# Power.net
KiCad netlist of a schematic drawn in Altium Designer
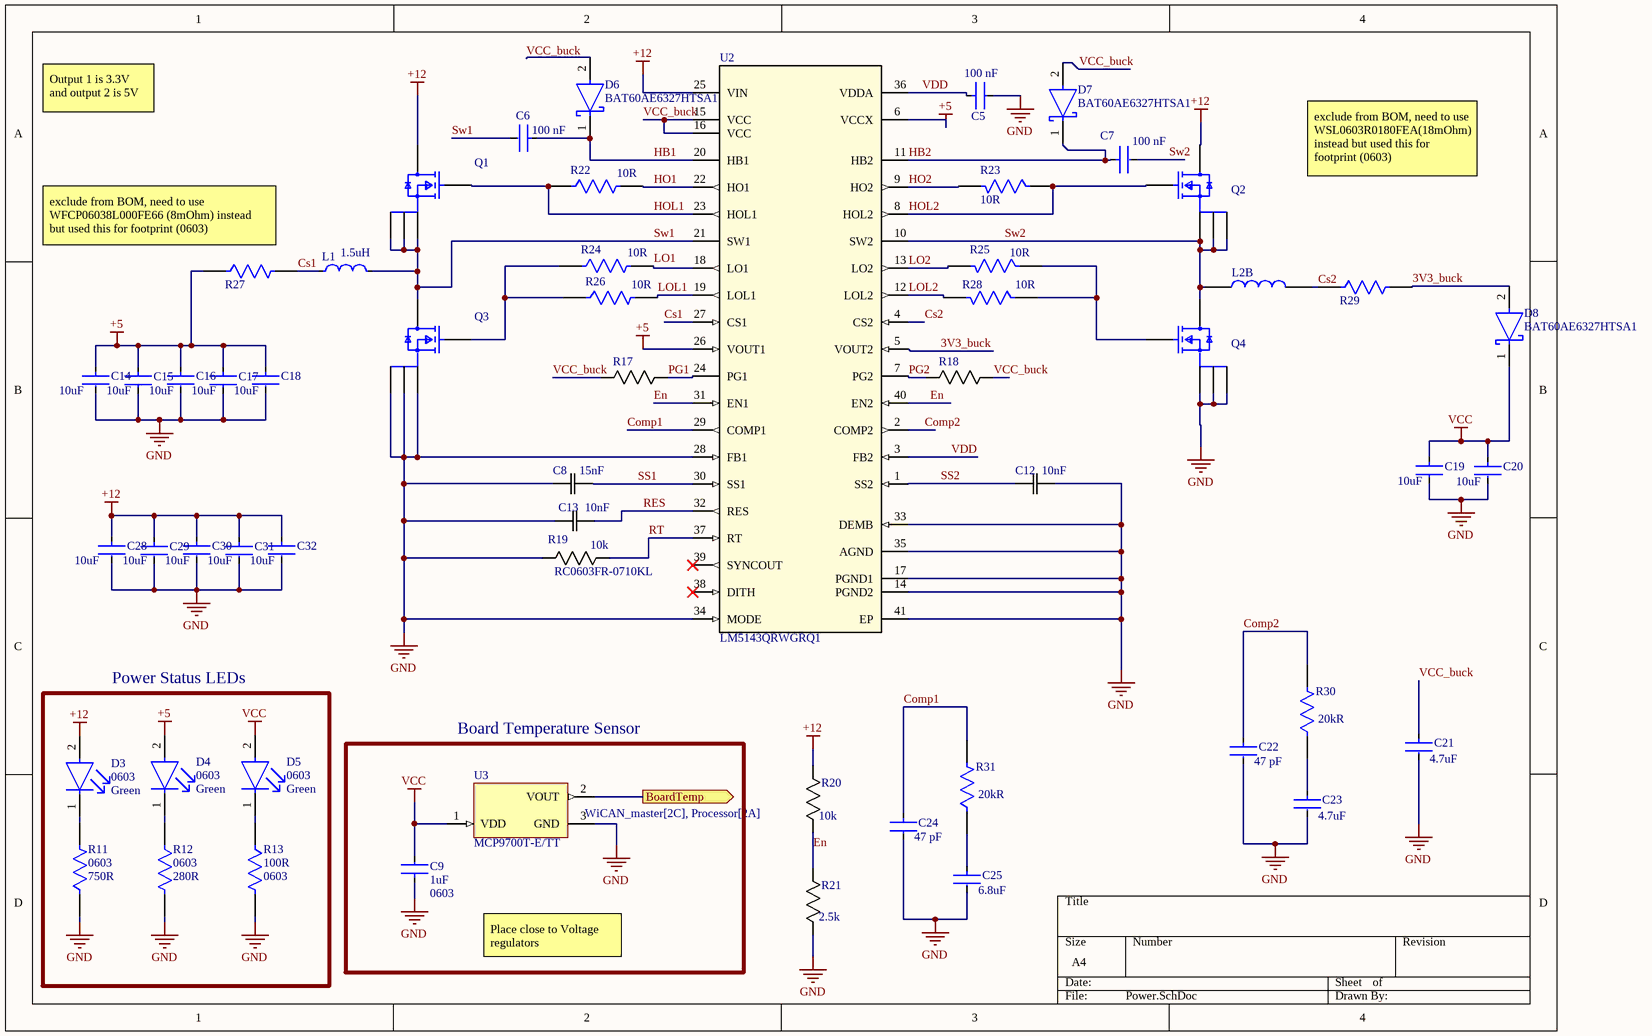
[diagram p0: Power.SchDoc]

(export (version "E")
  (design (tool "Eeschema 10.0.6"))
  (components
    (comp (ref "C5")
      (value "CC0603KRX7R8BB104")
      (footprint "FP-CC0603-DA-MFG")
      (description "CAP CER 0.1UF 25V X7R 0603")
      (fields
        (field (name "CAPACITANCE") "100 nF")
        (field (name "MANUFACTURER") "YAGEO")
        (field (name "OCTOPART") "https://octopart.com/cc0603krx7r8bb104-yageo-8376534")
      )
      (libsource (lib "Altium Content Vault") (part "11868f565c42a9108669ba33697ecf6"))
    )
    (comp (ref "C6")
      (value "CC0603KRX7R8BB104")
      (footprint "FP-CC0603-DA-MFG")
      (description "CAP CER 0.1UF 25V X7R 0603")
      (fields
        (field (name "CAPACITANCE") "100 nF")
        (field (name "MANUFACTURER") "YAGEO")
        (field (name "OCTOPART") "https://octopart.com/cc0603krx7r8bb104-yageo-8376534")
      )
      (libsource (lib "Altium Content Vault") (part "11868f565c42a9108669ba33697ecf6"))
    )
    (comp (ref "C7")
      (value "CC0603KRX7R8BB104")
      (footprint "FP-CC0603-DA-MFG")
      (description "CAP CER 0.1UF 25V X7R 0603")
      (fields
        (field (name "CAPACITANCE") "100 nF")
        (field (name "MANUFACTURER") "YAGEO")
        (field (name "OCTOPART") "https://octopart.com/cc0603krx7r8bb104-yageo-8376534")
      )
      (libsource (lib "Altium Content Vault") (part "11868f565c42a9108669ba33697ecf6"))
    )
    (comp (ref "C8")
      (value "C0603C153K5RACTU")
      (footprint "CAPC17595_87N_KEM")
      (description "SMD Comm X7R, Ceramic, 0.015 uF, 10%, 50 VDC, X7R, SMD, MLCC, Temperature Stable, Class II, 0603")
      (fields
        (field (name "CAPACITANCE") "15nF")
        (field (name "COPYRIGHT") "Copyright (C) 2026 Ultra Librarian. All rights reserved.")
      )
      (libsource (lib "WiCAN_lib") (part "C0603C153K5RACTU"))
    )
    (comp (ref "C9")
      (value "CL10A105KO8NNNC")
      (footprint "FP-CL10-IPC_A")
      (description "Cap Ceramic 1uF 16V X5R ±10% Pad SMD 0603 +85°C T/R")
      (fields
        (field (name "CAPACITANCE") "1uF")
        (field (name "CASE CODE (IMPERIAL)") "0603")
        (field (name "TOLERANCE") "10%")
        (field (name "VOLTAGE") "16V")
      )
      (libsource (lib "Altium Content Vault") (part "b4654b650e69147ec39a6b967a45e02"))
    )
    (comp (ref "C12")
      (value "C0603C153K5RACTU")
      (footprint "CAPC17595_87N_KEM")
      (description "SMD Comm X7R, Ceramic, 0.015 uF, 10%, 50 VDC, X7R, SMD, MLCC, Temperature Stable, Class II, 0603")
      (fields
        (field (name "CAPACITANCE") "10nF")
        (field (name "COPYRIGHT") "Copyright (C) 2026 Ultra Librarian. All rights reserved.")
      )
      (libsource (lib "WiCAN_lib") (part "C0603C153K5RACTU"))
    )
    (comp (ref "C13")
      (value "C0603C103K5RACTU")
      (footprint "CAPC17595_87N_KEM")
      (description "SMD Comm X7R, Ceramic, 0.01 uF, 10%, 50 VDC, X7R, SMD, MLCC, Temperature Stable, Class II, 0603")
      (fields
        (field (name "CAPACITANCE") "10nF")
        (field (name "COPYRIGHT") "Copyright (C) 2025 Ultra Librarian. All rights reserved.")
      )
      (libsource (lib "WiCAN_lib") (part "C0603C103K5RACTU"))
    )
    (comp (ref "C14")
      (value "GRM188R61A106ME69D")
      (footprint "FP-GRM188-0_15-MFG")
      (description "Chip Multilayer Ceramic Capacitors for General Purpose, 0603, 10uF, X5R, 15%, 20%, 10V")
      (fields (field (name "TOLERANCE") "20%") (field (name "CAPACITANCE") "10uF"))
      (libsource (lib "Altium Content Vault") (part "02cd4be3c70576c341d710602a673aa"))
    )
    (comp (ref "C15")
      (value "GRM188R61A106ME69D")
      (footprint "FP-GRM188-0_15-MFG")
      (description "Chip Multilayer Ceramic Capacitors for General Purpose, 0603, 10uF, X5R, 15%, 20%, 10V")
      (fields (field (name "TOLERANCE") "20%") (field (name "CAPACITANCE") "10uF"))
      (libsource (lib "Altium Content Vault") (part "02cd4be3c70576c341d710602a673aa"))
    )
    (comp (ref "C16")
      (value "GRM188R61A106ME69D")
      (footprint "FP-GRM188-0_15-MFG")
      (description "Chip Multilayer Ceramic Capacitors for General Purpose, 0603, 10uF, X5R, 15%, 20%, 10V")
      (fields (field (name "TOLERANCE") "20%") (field (name "CAPACITANCE") "10uF"))
      (libsource (lib "Altium Content Vault") (part "02cd4be3c70576c341d710602a673aa"))
    )
    (comp (ref "C17")
      (value "GRM188R61A106ME69D")
      (footprint "FP-GRM188-0_15-MFG")
      (description "Chip Multilayer Ceramic Capacitors for General Purpose, 0603, 10uF, X5R, 15%, 20%, 10V")
      (fields (field (name "TOLERANCE") "20%") (field (name "CAPACITANCE") "10uF"))
      (libsource (lib "Altium Content Vault") (part "02cd4be3c70576c341d710602a673aa"))
    )
    (comp (ref "C18")
      (value "GRM188R61A106ME69D")
      (footprint "FP-GRM188-0_15-MFG")
      (description "Chip Multilayer Ceramic Capacitors for General Purpose, 0603, 10uF, X5R, 15%, 20%, 10V")
      (fields (field (name "TOLERANCE") "20%") (field (name "CAPACITANCE") "10uF"))
      (libsource (lib "Altium Content Vault") (part "02cd4be3c70576c341d710602a673aa"))
    )
    (comp (ref "C19")
      (value "GRM188R61A106ME69D")
      (footprint "FP-GRM188-0_15-MFG")
      (description "Chip Multilayer Ceramic Capacitors for General Purpose, 0603, 10uF, X5R, 15%, 20%, 10V")
      (fields (field (name "TOLERANCE") "20%") (field (name "CAPACITANCE") "10uF"))
      (libsource (lib "Altium Content Vault") (part "02cd4be3c70576c341d710602a673aa"))
    )
    (comp (ref "C20")
      (value "GRM188R61A106ME69D")
      (footprint "FP-GRM188-0_15-MFG")
      (description "Chip Multilayer Ceramic Capacitors for General Purpose, 0603, 10uF, X5R, 15%, 20%, 10V")
      (fields (field (name "TOLERANCE") "20%") (field (name "CAPACITANCE") "10uF"))
      (libsource (lib "Altium Content Vault") (part "02cd4be3c70576c341d710602a673aa"))
    )
    (comp (ref "C21")
      (value "GRM188R61E475KE11D")
      (footprint "FP-GRM188-0_15-IPC_C")
      (description "Chip Multilayer Ceramic Capacitors for General Purpose, 0603, 4.7uF, X5R, 15%, 10%, 25V")
      (fields
        (field (name "CAPACITANCE") "4.7uF")
        (field (name "VOLTAGE") "25V")
        (field (name "TOLERANCE") "10%")
      )
      (libsource (lib "Altium Content Vault") (part "02cd4be3c70576c341d710602a673aa"))
    )
    (comp (ref "C22")
      (value "C0603C470J5GACTU")
      (footprint "FP-C0603C-CF-MFG")
      (description "CAP CER 47PF 50V C0G/NP0 0603")
      (fields
        (field (name "CAPACITANCE") "47 pF")
        (field (name "TOLERANCE") "0.05")
        (field (name "MANUFACTURER") "KEMET")
      )
      (libsource (lib "Altium Content Vault") (part "b4654b650e69147ec39a6b967a45e02"))
    )
    (comp (ref "C23")
      (value "GRM188R61E475KE11D")
      (footprint "FP-GRM188-0_15-IPC_C")
      (description "Chip Multilayer Ceramic Capacitors for General Purpose, 0603, 4.7uF, X5R, 15%, 10%, 25V")
      (fields
        (field (name "CAPACITANCE") "4.7uF")
        (field (name "VOLTAGE") "25V")
        (field (name "TOLERANCE") "10%")
      )
      (libsource (lib "Altium Content Vault") (part "02cd4be3c70576c341d710602a673aa"))
    )
    (comp (ref "C24")
      (value "C0603C470J5GACTU")
      (footprint "FP-C0603C-CF-MFG")
      (description "CAP CER 47PF 50V C0G/NP0 0603")
      (fields
        (field (name "CAPACITANCE") "47 pF")
        (field (name "TOLERANCE") "0.05")
        (field (name "MANUFACTURER") "KEMET")
      )
      (libsource (lib "Altium Content Vault") (part "b4654b650e69147ec39a6b967a45e02"))
    )
    (comp (ref "C25")
      (value "C1608X5R1A685M080AC")
      (footprint "FP-C1608-080-0_1-IPC_B")
      (description "Multilayer Ceramic Capacitors 6.8μF ±20% 10V X5R SMD 0603")
      (fields (field (name "CAPACITANCE") "6.8uF") (field (name "TOLERANCE") "20%"))
      (libsource (lib "Altium Content Vault") (part "236180d848d6139a670b325ea6854c9"))
    )
    (comp (ref "C28")
      (value "GRM188R61A106ME69D")
      (footprint "FP-GRM188-0_15-MFG")
      (description "Chip Multilayer Ceramic Capacitors for General Purpose, 0603, 10uF, X5R, 15%, 20%, 10V")
      (fields (field (name "TOLERANCE") "20%") (field (name "CAPACITANCE") "10uF"))
      (libsource (lib "Altium Content Vault") (part "02cd4be3c70576c341d710602a673aa"))
    )
    (comp (ref "C29")
      (value "GRM188R61A106ME69D")
      (footprint "FP-GRM188-0_15-MFG")
      (description "Chip Multilayer Ceramic Capacitors for General Purpose, 0603, 10uF, X5R, 15%, 20%, 10V")
      (fields (field (name "TOLERANCE") "20%") (field (name "CAPACITANCE") "10uF"))
      (libsource (lib "Altium Content Vault") (part "02cd4be3c70576c341d710602a673aa"))
    )
    (comp (ref "C30")
      (value "GRM188R61A106ME69D")
      (footprint "FP-GRM188-0_15-MFG")
      (description "Chip Multilayer Ceramic Capacitors for General Purpose, 0603, 10uF, X5R, 15%, 20%, 10V")
      (fields (field (name "TOLERANCE") "20%") (field (name "CAPACITANCE") "10uF"))
      (libsource (lib "Altium Content Vault") (part "02cd4be3c70576c341d710602a673aa"))
    )
    (comp (ref "C31")
      (value "GRM188R61A106ME69D")
      (footprint "FP-GRM188-0_15-MFG")
      (description "Chip Multilayer Ceramic Capacitors for General Purpose, 0603, 10uF, X5R, 15%, 20%, 10V")
      (fields (field (name "TOLERANCE") "20%") (field (name "CAPACITANCE") "10uF"))
      (libsource (lib "Altium Content Vault") (part "02cd4be3c70576c341d710602a673aa"))
    )
    (comp (ref "C32")
      (value "GRM188R61A106ME69D")
      (footprint "FP-GRM188-0_15-MFG")
      (description "Chip Multilayer Ceramic Capacitors for General Purpose, 0603, 10uF, X5R, 15%, 20%, 10V")
      (fields (field (name "TOLERANCE") "20%") (field (name "CAPACITANCE") "10uF"))
      (libsource (lib "Altium Content Vault") (part "02cd4be3c70576c341d710602a673aa"))
    )
    (comp (ref "D3")
      (value "12V")
      (footprint "FP-LTST-C190KGKT-MFG")
      (description "LED GREEN CLEAR CHIP SMD")
      (fields (field (name "CASE CODE (IMPERIAL)") "0603") (field (name "COLOR") "Green"))
      (libsource (lib "Altium Content Vault") (part "8706943c75ba83719d021d2fdc84c58"))
    )
    (comp (ref "D4")
      (value "5V")
      (footprint "FP-LTST-C190KGKT-MFG")
      (description "LED GREEN CLEAR CHIP SMD")
      (fields (field (name "CASE CODE (IMPERIAL)") "0603") (field (name "COLOR") "Green"))
      (libsource (lib "Altium Content Vault") (part "8706943c75ba83719d021d2fdc84c58"))
    )
    (comp (ref "D5")
      (value "3V3")
      (footprint "FP-LTST-C190KGKT-MFG")
      (description "LED GREEN CLEAR CHIP SMD")
      (fields (field (name "CASE CODE (IMPERIAL)") "0603") (field (name "COLOR") "Green"))
      (libsource (lib "Altium Content Vault") (part "8706943c75ba83719d021d2fdc84c58"))
    )
    (comp (ref "D6")
      (value "BAT60AE6327HTSA1")
      (footprint "FP-PG-SOD323-2-IPC_C")
      (description "DIODE SCHOTTKY 10V 3A SOD323-2")
      (libsource (lib "Altium Content Vault") (part "1d6ec82d83fb6aee721767c19dac4b9"))
    )
    (comp (ref "D7")
      (value "BAT60AE6327HTSA1")
      (footprint "FP-PG-SOD323-2-IPC_C")
      (description "DIODE SCHOTTKY 10V 3A SOD323-2")
      (libsource (lib "Altium Content Vault") (part "1d6ec82d83fb6aee721767c19dac4b9"))
    )
    (comp (ref "D8")
      (value "BAT60AE6327HTSA1")
      (footprint "FP-PG-SOD323-2-IPC_C")
      (description "DIODE SCHOTTKY 10V 3A SOD323-2")
      (libsource (lib "Altium Content Vault") (part "1d6ec82d83fb6aee721767c19dac4b9"))
    )
    (comp (ref "L1")
      (value "1.5uH")
      (footprint "FP-PCC-M0530M-LP-MFG")
      (description "FIXED IND 1.5UH 8.1A 13.2 MOHM")
      (fields
        (field (name "OCTOPART") "https://octopart.com/etq-p3m1r5kvp-panasonic-74144444")
        (field (name "TOLERANCE") "20%")
      )
      (libsource (lib "Altium Content Vault") (part "725321dda6339637d4d059423bc1c3c"))
    )
    (comp (ref "L2")
      (value "CDRH104RNP-2R5NC")
      (footprint "CDRH104RNP-2R5NC")
      (description "FIXED IND 2.5UH 6.1A 10.5 MOHM")
      (libsource (lib "WiCAN_lib") (part "CDRH104RNP-2R5NC"))
    )
    (comp (ref "Q1")
      (value "CSD17579Q3A")
      (footprint "FP-DNH0008A-MFG")
      (description "MOSFET N-CH 30V 35A 8VSON")
      (libsource (lib "Altium Content Vault") (part "2f22917ac7dd3b73ce0e75a3671b7f7"))
    )
    (comp (ref "Q2")
      (value "CSD17579Q3A")
      (footprint "FP-DNH0008A-MFG")
      (description "MOSFET N-CH 30V 35A 8VSON")
      (libsource (lib "Altium Content Vault") (part "2f22917ac7dd3b73ce0e75a3671b7f7"))
    )
    (comp (ref "Q3")
      (value "CSD17579Q3A")
      (footprint "FP-DNH0008A-MFG")
      (description "MOSFET N-CH 30V 35A 8VSON")
      (libsource (lib "Altium Content Vault") (part "2f22917ac7dd3b73ce0e75a3671b7f7"))
    )
    (comp (ref "Q4")
      (value "CSD17579Q3A")
      (footprint "FP-DNH0008A-MFG")
      (description "MOSFET N-CH 30V 35A 8VSON")
      (libsource (lib "Altium Content Vault") (part "2f22917ac7dd3b73ce0e75a3671b7f7"))
    )
    (comp (ref "R11")
      (value "ESR03EZPJ751")
      (footprint "FP-ESR03-IPC_B")
      (description "750Ω ±5% 0.25W 0603 Anti-Surge Chip Resistor AEC-Q200")
      (fields
        (field (name "CASE/PACKAGE") "0603")
        (field (name "RESISTANCE") "750R")
        (field (name "TOLERANCE") "5%")
      )
      (libsource (lib "Altium Content Vault") (part "1029c3af85768c4190bb7ad29bc67b5"))
    )
    (comp (ref "R12")
      (value "RMCF0603FT280R")
      (footprint "FP-RMCF0603-MFG")
      (description "280Ω ±1% 0.1W 0603 Thick Film Chip Resistor AEC-Q200 compliant")
      (fields
        (field (name "CASE/PACKAGE") "0603")
        (field (name "TOLERANCE") "1%")
        (field (name "RESISTANCE") "280R")
      )
      (libsource (lib "Altium Content Vault") (part "1029c3af85768c4190bb7ad29bc67b5"))
    )
    (comp (ref "R13")
      (value "AC0603FR-10100RL")
      (footprint "FP-AC0603-IPC_A")
      (description "RES 100Ω 1.00% 0.1W 0603")
      (fields
        (field (name "TOLERANCE") "1%")
        (field (name "RESISTANCE") "100R")
        (field (name "CASE/PACKAGE") "0603")
      )
      (libsource (lib "Altium Content Vault") (part "1029c3af85768c4190bb7ad29bc67b5"))
    )
    (comp (ref "R17")
      (value "RC0603FR-0710KL")
      (footprint "RC0603N_YAG")
      (description "RES SMD 10kO 1% 1/10W 0603")
      (fields (field (name "COPYRIGHT") "Copyright (C) 2025 Ultra Librarian. All rights reserved."))
      (libsource (lib "WiCAN_lib") (part "RC0603FR-0710KL"))
    )
    (comp (ref "R18")
      (value "RC0603FR-0710KL")
      (footprint "RC0603N_YAG")
      (description "RES SMD 10kO 1% 1/10W 0603")
      (fields (field (name "COPYRIGHT") "Copyright (C) 2025 Ultra Librarian. All rights reserved."))
      (libsource (lib "WiCAN_lib") (part "RC0603FR-0710KL"))
    )
    (comp (ref "R19")
      (value "RC0603FR-0710KL")
      (footprint "RC0603N_YAG")
      (description "RES SMD 10kO 1% 1/10W 0603")
      (fields
        (field (name "R") "10k")
        (field (name "COPYRIGHT") "Copyright (C) 2025 Ultra Librarian. All rights reserved.")
      )
      (libsource (lib "WiCAN_lib") (part "RC0603FR-0710KL"))
    )
    (comp (ref "R20")
      (value "RC0603FR-0710KL")
      (footprint "RC0603N_YAG")
      (description "RES SMD 10kO 1% 1/10W 0603")
      (fields
        (field (name "R") "10k")
        (field (name "COPYRIGHT") "Copyright (C) 2025 Ultra Librarian. All rights reserved.")
      )
      (libsource (lib "WiCAN_lib") (part "RC0603FR-0710KL"))
    )
    (comp (ref "R21")
      (value "RNCF0603BTE2K50")
      (footprint "RES_RNCF0603_STP")
      (description "RES SMD 2.5K OHM 0.1% 1/6W 0603")
      (fields
        (field (name "R") "2.5k")
        (field (name "COPYRIGHT") "Copyright (C) 2025 Ultra Librarian. All rights reserved.")
      )
      (libsource (lib "WiCAN_lib") (part "RNCF0603BTE2K50"))
    )
    (comp (ref "R22")
      (value "RMCF0603FT10R0")
      (footprint "FP-RMCF0603-MFG")
      (description "10Ω ±1% 0.1W 0603 Thick Film Chip Resistor AEC-Q200 compliant")
      (fields (field (name "TOLERANCE") "1%") (field (name "RESISTANCE") "10R"))
      (libsource (lib "Altium Content Vault") (part "1029c3af85768c4190bb7ad29bc67b5"))
    )
    (comp (ref "R23")
      (value "RMCF0603FT10R0")
      (footprint "FP-RMCF0603-MFG")
      (description "10Ω ±1% 0.1W 0603 Thick Film Chip Resistor AEC-Q200 compliant")
      (fields (field (name "TOLERANCE") "1%") (field (name "RESISTANCE") "10R"))
      (libsource (lib "Altium Content Vault") (part "1029c3af85768c4190bb7ad29bc67b5"))
    )
    (comp (ref "R24")
      (value "RMCF0603FT10R0")
      (footprint "FP-RMCF0603-MFG")
      (description "10Ω ±1% 0.1W 0603 Thick Film Chip Resistor AEC-Q200 compliant")
      (fields (field (name "TOLERANCE") "1%") (field (name "RESISTANCE") "10R"))
      (libsource (lib "Altium Content Vault") (part "1029c3af85768c4190bb7ad29bc67b5"))
    )
    (comp (ref "R25")
      (value "RMCF0603FT10R0")
      (footprint "FP-RMCF0603-MFG")
      (description "10Ω ±1% 0.1W 0603 Thick Film Chip Resistor AEC-Q200 compliant")
      (fields (field (name "TOLERANCE") "1%") (field (name "RESISTANCE") "10R"))
      (libsource (lib "Altium Content Vault") (part "1029c3af85768c4190bb7ad29bc67b5"))
    )
    (comp (ref "R26")
      (value "RMCF0603FT10R0")
      (footprint "FP-RMCF0603-MFG")
      (description "10Ω ±1% 0.1W 0603 Thick Film Chip Resistor AEC-Q200 compliant")
      (fields (field (name "TOLERANCE") "1%") (field (name "RESISTANCE") "10R"))
      (libsource (lib "Altium Content Vault") (part "1029c3af85768c4190bb7ad29bc67b5"))
    )
    (comp (ref "R27")
      (value "MCT0603MD4021BP100")
      (footprint "FP-MCT0603-MFG")
      (description "RES SMD 100 OHM 1% 1/8W 0603")
      (fields (field (name "TOLERANCE") "0.1%"))
      (libsource (lib "Altium Content Vault") (part "1029c3af85768c4190bb7ad29bc67b5"))
    )
    (comp (ref "R28")
      (value "RMCF0603FT10R0")
      (footprint "FP-RMCF0603-MFG")
      (description "10Ω ±1% 0.1W 0603 Thick Film Chip Resistor AEC-Q200 compliant")
      (fields (field (name "TOLERANCE") "1%") (field (name "RESISTANCE") "10R"))
      (libsource (lib "Altium Content Vault") (part "1029c3af85768c4190bb7ad29bc67b5"))
    )
    (comp (ref "R29")
      (value "MCT0603MD4021BP100")
      (footprint "FP-MCT0603-MFG")
      (description "RES SMD 100 OHM 1% 1/8W 0603")
      (fields (field (name "TOLERANCE") "0.1%"))
      (libsource (lib "Altium Content Vault") (part "1029c3af85768c4190bb7ad29bc67b5"))
    )
    (comp (ref "R30")
      (value "RC0603FR-0720KL")
      (footprint "FP-RC0603-0_55-IPC_C")
      (description "RES 20K OHM 1% 1/10W 0603")
      (fields (field (name "TOLERANCE") "1%") (field (name "RESISTANCE") "20kR"))
      (libsource (lib "Altium Content Vault") (part "1029c3af85768c4190bb7ad29bc67b5"))
    )
    (comp (ref "R31")
      (value "RC0603FR-0720KL")
      (footprint "FP-RC0603-0_55-IPC_C")
      (description "RES 20K OHM 1% 1/10W 0603")
      (fields (field (name "TOLERANCE") "1%") (field (name "RESISTANCE") "20kR"))
      (libsource (lib "Altium Content Vault") (part "1029c3af85768c4190bb7ad29bc67b5"))
    )
    (comp (ref "U2")
      (value "LM5143QRWGRQ1")
      (footprint "RWG0040A")
      (description "3.5-V to 65-V low Iq, dual, 2-phase synchronous buck DC-DC controller 40-VQFNP -40 to 150")
      (fields (field (name "COPYRIGHT") "Copyright (C) 2026 Ultra Librarian. All rights reserved."))
      (libsource (lib "WiCAN_lib") (part "LM5143QRWGRQ1"))
    )
    (comp (ref "U3")
      (value "MCP9700T-E/TT")
      (footprint "SOT-23-TT3_M")
      (description "Low-Power Linear Active Thermistor IC, 3-Pin SOT-23, Extended Temperature, Tape and Reel")
      (libsource (lib "Altium Content Vault") (part "SEN-TEMP-MCP9700-3"))
    )
  )
  (nets
    (net (code "1") (name "+5") (class "Default")
      (node (ref "C14") (pin "1") (pinfunction "1_1") (pintype "passive"))
      (node (ref "C15") (pin "1") (pinfunction "1_1") (pintype "passive"))
      (node (ref "C16") (pin "1") (pinfunction "1_1") (pintype "passive"))
      (node (ref "C17") (pin "1") (pinfunction "1_1") (pintype "passive"))
      (node (ref "C18") (pin "1") (pinfunction "1_1") (pintype "passive"))
      (node (ref "D4") (pin "2") (pinfunction "A_2") (pintype "passive"))
      (node (ref "R27") (pin "1") (pinfunction "1_1") (pintype "passive"))
      (node (ref "U2") (pin "26") (pinfunction "VOUT1_26") (pintype "input"))
      (node (ref "U2") (pin "6") (pinfunction "VCCX_6") (pintype "power_in"))
    )
    (net (code "2") (name "+12") (class "Default")
      (node (ref "C28") (pin "1") (pinfunction "1_1") (pintype "passive"))
      (node (ref "C29") (pin "1") (pinfunction "1_1") (pintype "passive"))
      (node (ref "C30") (pin "1") (pinfunction "1_1") (pintype "passive"))
      (node (ref "C31") (pin "1") (pinfunction "1_1") (pintype "passive"))
      (node (ref "C32") (pin "1") (pinfunction "1_1") (pintype "passive"))
      (node (ref "D3") (pin "2") (pinfunction "A_2") (pintype "passive"))
      (node (ref "Q1") (pin "5-6-7-8") (pinfunction "D_5-6-7-8") (pintype "passive"))
      (node (ref "Q2") (pin "5-6-7-8") (pinfunction "D_5-6-7-8") (pintype "passive"))
      (node (ref "R20") (pin "2") (pinfunction "2_2") (pintype "passive"))
      (node (ref "U2") (pin "25") (pinfunction "VIN_25") (pintype "power_in"))
    )
    (net (code "3") (name "/3V3_buck") (class "Default")
      (node (ref "D8") (pin "2") (pinfunction "A_2") (pintype "passive"))
      (node (ref "R29") (pin "2") (pinfunction "2_2") (pintype "passive"))
      (node (ref "U2") (pin "5") (pinfunction "VOUT2_5") (pintype "input"))
    )
    (net (code "4") (name "/BoardTemp") (class "Default")
      (node (ref "U3") (pin "2") (pinfunction "VOUT_2") (pintype "output"))
    )
    (net (code "5") (name "/Comp1") (class "Default")
      (node (ref "C24") (pin "1") (pinfunction "1_1") (pintype "passive"))
      (node (ref "R31") (pin "2") (pinfunction "2_2") (pintype "passive"))
      (node (ref "U2") (pin "29") (pinfunction "COMP1_29") (pintype "output"))
    )
    (net (code "6") (name "/Comp2") (class "Default")
      (node (ref "C22") (pin "1") (pinfunction "1_1") (pintype "passive"))
      (node (ref "R30") (pin "2") (pinfunction "2_2") (pintype "passive"))
      (node (ref "U2") (pin "2") (pinfunction "COMP2_2") (pintype "output"))
    )
    (net (code "7") (name "/Cs1") (class "Default")
      (node (ref "L1") (pin "1") (pinfunction "1_1") (pintype "passive"))
      (node (ref "R27") (pin "2") (pinfunction "2_2") (pintype "passive"))
      (node (ref "U2") (pin "27") (pinfunction "CS1_27") (pintype "input"))
    )
    (net (code "8") (name "/Cs2") (class "Default")
      (node (ref "L2") (pin "2") (pinfunction "2_2") (pintype "passive"))
      (node (ref "R29") (pin "1") (pinfunction "1_1") (pintype "passive"))
      (node (ref "U2") (pin "4") (pinfunction "CS2_4") (pintype "input"))
    )
    (net (code "9") (name "/En") (class "Default")
      (node (ref "R20") (pin "1") (pinfunction "1_1") (pintype "passive"))
      (node (ref "R21") (pin "2") (pinfunction "2_2") (pintype "passive"))
      (node (ref "U2") (pin "31") (pinfunction "EN1_31") (pintype "input"))
      (node (ref "U2") (pin "40") (pinfunction "EN2_40") (pintype "input"))
    )
    (net (code "10") (name "/HB1") (class "Default")
      (node (ref "C6") (pin "1") (pinfunction "1_1") (pintype "passive"))
      (node (ref "D6") (pin "1") (pinfunction "C_1") (pintype "passive"))
      (node (ref "U2") (pin "20") (pinfunction "HB1_20") (pintype "power_in"))
    )
    (net (code "11") (name "/HB2") (class "Default")
      (node (ref "C7") (pin "1") (pinfunction "1_1") (pintype "passive"))
      (node (ref "D7") (pin "1") (pinfunction "C_1") (pintype "passive"))
      (node (ref "U2") (pin "11") (pinfunction "HB2_11") (pintype "power_in"))
    )
    (net (code "12") (name "/HO1") (class "Default")
      (node (ref "R22") (pin "2") (pinfunction "2_2") (pintype "passive"))
      (node (ref "U2") (pin "22") (pinfunction "HO1_22") (pintype "output"))
    )
    (net (code "13") (name "/HO2") (class "Default")
      (node (ref "R23") (pin "2") (pinfunction "2_2") (pintype "passive"))
      (node (ref "U2") (pin "9") (pinfunction "HO2_9") (pintype "output"))
    )
    (net (code "14") (name "/HOL1") (class "Default")
      (node (ref "Q1") (pin "4") (pinfunction "G_4") (pintype "passive"))
      (node (ref "R22") (pin "1") (pinfunction "1_1") (pintype "passive"))
      (node (ref "U2") (pin "23") (pinfunction "HOL1_23") (pintype "output"))
    )
    (net (code "15") (name "/HOL2") (class "Default")
      (node (ref "Q2") (pin "4") (pinfunction "G_4") (pintype "passive"))
      (node (ref "R23") (pin "1") (pinfunction "1_1") (pintype "passive"))
      (node (ref "U2") (pin "8") (pinfunction "HOL2_8") (pintype "output"))
    )
    (net (code "16") (name "/LO1") (class "Default")
      (node (ref "R24") (pin "2") (pinfunction "2_2") (pintype "passive"))
      (node (ref "U2") (pin "18") (pinfunction "LO1_18") (pintype "output"))
    )
    (net (code "17") (name "/LO2") (class "Default")
      (node (ref "R25") (pin "2") (pinfunction "2_2") (pintype "passive"))
      (node (ref "U2") (pin "13") (pinfunction "LO2_13") (pintype "output"))
    )
    (net (code "18") (name "/LOL1") (class "Default")
      (node (ref "R26") (pin "2") (pinfunction "2_2") (pintype "passive"))
      (node (ref "U2") (pin "19") (pinfunction "LOL1_19") (pintype "output"))
    )
    (net (code "19") (name "/LOL2") (class "Default")
      (node (ref "R28") (pin "2") (pinfunction "2_2") (pintype "passive"))
      (node (ref "U2") (pin "12") (pinfunction "LOL2_12") (pintype "output"))
    )
    (net (code "20") (name "/PG1") (class "Default")
      (node (ref "R17") (pin "2") (pinfunction "2_2") (pintype "passive"))
      (node (ref "U2") (pin "24") (pinfunction "PG1_24") (pintype "open_collector"))
    )
    (net (code "21") (name "/PG2") (class "Default")
      (node (ref "R18") (pin "1") (pinfunction "1_1") (pintype "passive"))
      (node (ref "U2") (pin "7") (pinfunction "PG2_7") (pintype "open_collector"))
    )
    (net (code "22") (name "/RES") (class "Default")
      (node (ref "C13") (pin "2") (pinfunction "2_2") (pintype "passive"))
      (node (ref "U2") (pin "32") (pinfunction "RES_32") (pintype "output"))
    )
    (net (code "23") (name "/RT") (class "Default")
      (node (ref "R19") (pin "2") (pinfunction "2_2") (pintype "passive"))
      (node (ref "U2") (pin "37") (pinfunction "RT_37") (pintype "input"))
    )
    (net (code "24") (name "/SS1") (class "Default")
      (node (ref "C8") (pin "2") (pinfunction "2_2") (pintype "passive"))
      (node (ref "U2") (pin "30") (pinfunction "SS1_30") (pintype "input"))
    )
    (net (code "25") (name "/SS2") (class "Default")
      (node (ref "C12") (pin "1") (pinfunction "1_1") (pintype "passive"))
      (node (ref "U2") (pin "1") (pinfunction "SS2_1") (pintype "input"))
    )
    (net (code "26") (name "/Sw1") (class "Default")
      (node (ref "C6") (pin "2") (pinfunction "2_2") (pintype "passive"))
      (node (ref "L1") (pin "2") (pinfunction "2_2") (pintype "passive"))
      (node (ref "Q1") (pin "1") (pinfunction "S_1") (pintype "passive"))
      (node (ref "Q1") (pin "2") (pinfunction "S_2") (pintype "passive"))
      (node (ref "Q1") (pin "3") (pinfunction "S_3") (pintype "passive"))
      (node (ref "Q3") (pin "5-6-7-8") (pinfunction "D_5-6-7-8") (pintype "passive"))
      (node (ref "U2") (pin "21") (pinfunction "SW1_21") (pintype "power_in"))
    )
    (net (code "27") (name "/Sw2") (class "Default")
      (node (ref "C7") (pin "2") (pinfunction "2_2") (pintype "passive"))
      (node (ref "L2") (pin "1") (pinfunction "1_1") (pintype "passive"))
      (node (ref "Q2") (pin "1") (pinfunction "S_1") (pintype "passive"))
      (node (ref "Q2") (pin "2") (pinfunction "S_2") (pintype "passive"))
      (node (ref "Q2") (pin "3") (pinfunction "S_3") (pintype "passive"))
      (node (ref "Q4") (pin "5-6-7-8") (pinfunction "D_5-6-7-8") (pintype "passive"))
      (node (ref "U2") (pin "10") (pinfunction "SW2_10") (pintype "power_in"))
    )
    (net (code "28") (name "/VCC_buck") (class "Default")
      (node (ref "C21") (pin "1") (pinfunction "1_1") (pintype "passive"))
      (node (ref "D6") (pin "2") (pinfunction "A_2") (pintype "passive"))
      (node (ref "D7") (pin "2") (pinfunction "A_2") (pintype "passive"))
      (node (ref "R17") (pin "1") (pinfunction "1_1") (pintype "passive"))
      (node (ref "R18") (pin "2") (pinfunction "2_2") (pintype "passive"))
      (node (ref "U2") (pin "15") (pinfunction "VCC_15") (pintype "power_in"))
      (node (ref "U2") (pin "16") (pinfunction "VCC_16") (pintype "power_in"))
    )
    (net (code "29") (name "/VDD") (class "Default")
      (node (ref "C5") (pin "1") (pinfunction "1_1") (pintype "passive"))
      (node (ref "U2") (pin "3") (pinfunction "FB2_3") (pintype "input"))
      (node (ref "U2") (pin "36") (pinfunction "VDDA_36") (pintype "power_in"))
    )
    (net (code "30") (name "GND") (class "Default")
      (node (ref "C12") (pin "2") (pinfunction "2_2") (pintype "passive"))
      (node (ref "C13") (pin "1") (pinfunction "1_1") (pintype "passive"))
      (node (ref "C14") (pin "2") (pinfunction "2_2") (pintype "passive"))
      (node (ref "C15") (pin "2") (pinfunction "2_2") (pintype "passive"))
      (node (ref "C16") (pin "2") (pinfunction "2_2") (pintype "passive"))
      (node (ref "C17") (pin "2") (pinfunction "2_2") (pintype "passive"))
      (node (ref "C18") (pin "2") (pinfunction "2_2") (pintype "passive"))
      (node (ref "C19") (pin "2") (pinfunction "2_2") (pintype "passive"))
      (node (ref "C20") (pin "2") (pinfunction "2_2") (pintype "passive"))
      (node (ref "C21") (pin "2") (pinfunction "2_2") (pintype "passive"))
      (node (ref "C22") (pin "2") (pinfunction "2_2") (pintype "passive"))
      (node (ref "C23") (pin "2") (pinfunction "2_2") (pintype "passive"))
      (node (ref "C24") (pin "2") (pinfunction "2_2") (pintype "passive"))
      (node (ref "C25") (pin "1") (pinfunction "1_1") (pintype "passive"))
      (node (ref "C28") (pin "2") (pinfunction "2_2") (pintype "passive"))
      (node (ref "C29") (pin "2") (pinfunction "2_2") (pintype "passive"))
      (node (ref "C30") (pin "2") (pinfunction "2_2") (pintype "passive"))
      (node (ref "C31") (pin "2") (pinfunction "2_2") (pintype "passive"))
      (node (ref "C32") (pin "2") (pinfunction "2_2") (pintype "passive"))
      (node (ref "C5") (pin "2") (pinfunction "2_2") (pintype "passive"))
      (node (ref "C8") (pin "1") (pinfunction "1_1") (pintype "passive"))
      (node (ref "C9") (pin "1") (pinfunction "1_1") (pintype "passive"))
      (node (ref "Q3") (pin "1") (pinfunction "S_1") (pintype "passive"))
      (node (ref "Q3") (pin "2") (pinfunction "S_2") (pintype "passive"))
      (node (ref "Q3") (pin "3") (pinfunction "S_3") (pintype "passive"))
      (node (ref "Q4") (pin "1") (pinfunction "S_1") (pintype "passive"))
      (node (ref "Q4") (pin "2") (pinfunction "S_2") (pintype "passive"))
      (node (ref "Q4") (pin "3") (pinfunction "S_3") (pintype "passive"))
      (node (ref "R11") (pin "1") (pinfunction "1_1") (pintype "passive"))
      (node (ref "R12") (pin "2") (pinfunction "2_2") (pintype "passive"))
      (node (ref "R13") (pin "2") (pinfunction "2_2") (pintype "passive"))
      (node (ref "R19") (pin "1") (pinfunction "1_1") (pintype "passive"))
      (node (ref "R21") (pin "1") (pinfunction "1_1") (pintype "passive"))
      (node (ref "U2") (pin "14") (pinfunction "PGND2_14") (pintype "power_in"))
      (node (ref "U2") (pin "17") (pinfunction "PGND1_17") (pintype "power_in"))
      (node (ref "U2") (pin "28") (pinfunction "FB1_28") (pintype "input"))
      (node (ref "U2") (pin "33") (pinfunction "DEMB_33") (pintype "input"))
      (node (ref "U2") (pin "34") (pinfunction "MODE_34") (pintype "input"))
      (node (ref "U2") (pin "35") (pinfunction "AGND_35") (pintype "power_in"))
      (node (ref "U2") (pin "41") (pinfunction "EP_41") (pintype "power_in"))
      (node (ref "U3") (pin "3") (pinfunction "GND_3") (pintype "power_in"))
    )
    (net (code "31") (name "Net-(C23-Pad1)") (class "Default")
      (node (ref "C23") (pin "1") (pinfunction "1_1") (pintype "passive"))
      (node (ref "R30") (pin "1") (pinfunction "1_1") (pintype "passive"))
    )
    (net (code "32") (name "Net-(C25-Pad2)") (class "Default")
      (node (ref "C25") (pin "2") (pinfunction "2_2") (pintype "passive"))
      (node (ref "R31") (pin "1") (pinfunction "1_1") (pintype "passive"))
    )
    (net (code "33") (name "Net-(D3-C)") (class "Default")
      (node (ref "D3") (pin "1") (pinfunction "C_1") (pintype "passive"))
      (node (ref "R11") (pin "2") (pinfunction "2_2") (pintype "passive"))
    )
    (net (code "34") (name "Net-(D4-C)") (class "Default")
      (node (ref "D4") (pin "1") (pinfunction "C_1") (pintype "passive"))
      (node (ref "R12") (pin "1") (pinfunction "1_1") (pintype "passive"))
    )
    (net (code "35") (name "Net-(D5-C)") (class "Default")
      (node (ref "D5") (pin "1") (pinfunction "C_1") (pintype "passive"))
      (node (ref "R13") (pin "1") (pinfunction "1_1") (pintype "passive"))
    )
    (net (code "36") (name "Net-(Q3-G)") (class "Default")
      (node (ref "Q3") (pin "4") (pinfunction "G_4") (pintype "passive"))
      (node (ref "R24") (pin "1") (pinfunction "1_1") (pintype "passive"))
      (node (ref "R26") (pin "1") (pinfunction "1_1") (pintype "passive"))
    )
    (net (code "37") (name "Net-(Q4-G)") (class "Default")
      (node (ref "Q4") (pin "4") (pinfunction "G_4") (pintype "passive"))
      (node (ref "R25") (pin "1") (pinfunction "1_1") (pintype "passive"))
      (node (ref "R28") (pin "1") (pinfunction "1_1") (pintype "passive"))
    )
    (net (code "38") (name "VCC") (class "Default")
      (node (ref "C19") (pin "1") (pinfunction "1_1") (pintype "passive"))
      (node (ref "C20") (pin "1") (pinfunction "1_1") (pintype "passive"))
      (node (ref "C9") (pin "2") (pinfunction "2_2") (pintype "passive"))
      (node (ref "D5") (pin "2") (pinfunction "A_2") (pintype "passive"))
      (node (ref "D8") (pin "1") (pinfunction "C_1") (pintype "passive"))
      (node (ref "U3") (pin "1") (pinfunction "VDD_1") (pintype "input"))
    )
    (net (code "39") (name "unconnected-(U2-DITH-Pad38)") (class "Default")
      (node (ref "U2") (pin "38") (pinfunction "DITH_38") (pintype "input+no_connect"))
    )
    (net (code "40") (name "unconnected-(U2-SYNCOUT-Pad39)") (class "Default")
      (node (ref "U2") (pin "39") (pinfunction "SYNCOUT_39") (pintype "output+no_connect"))
    )
  )
)
